# Nodo_actuador_wa4_v1.net
KiCad netlist of a schematic drawn in EAGLE
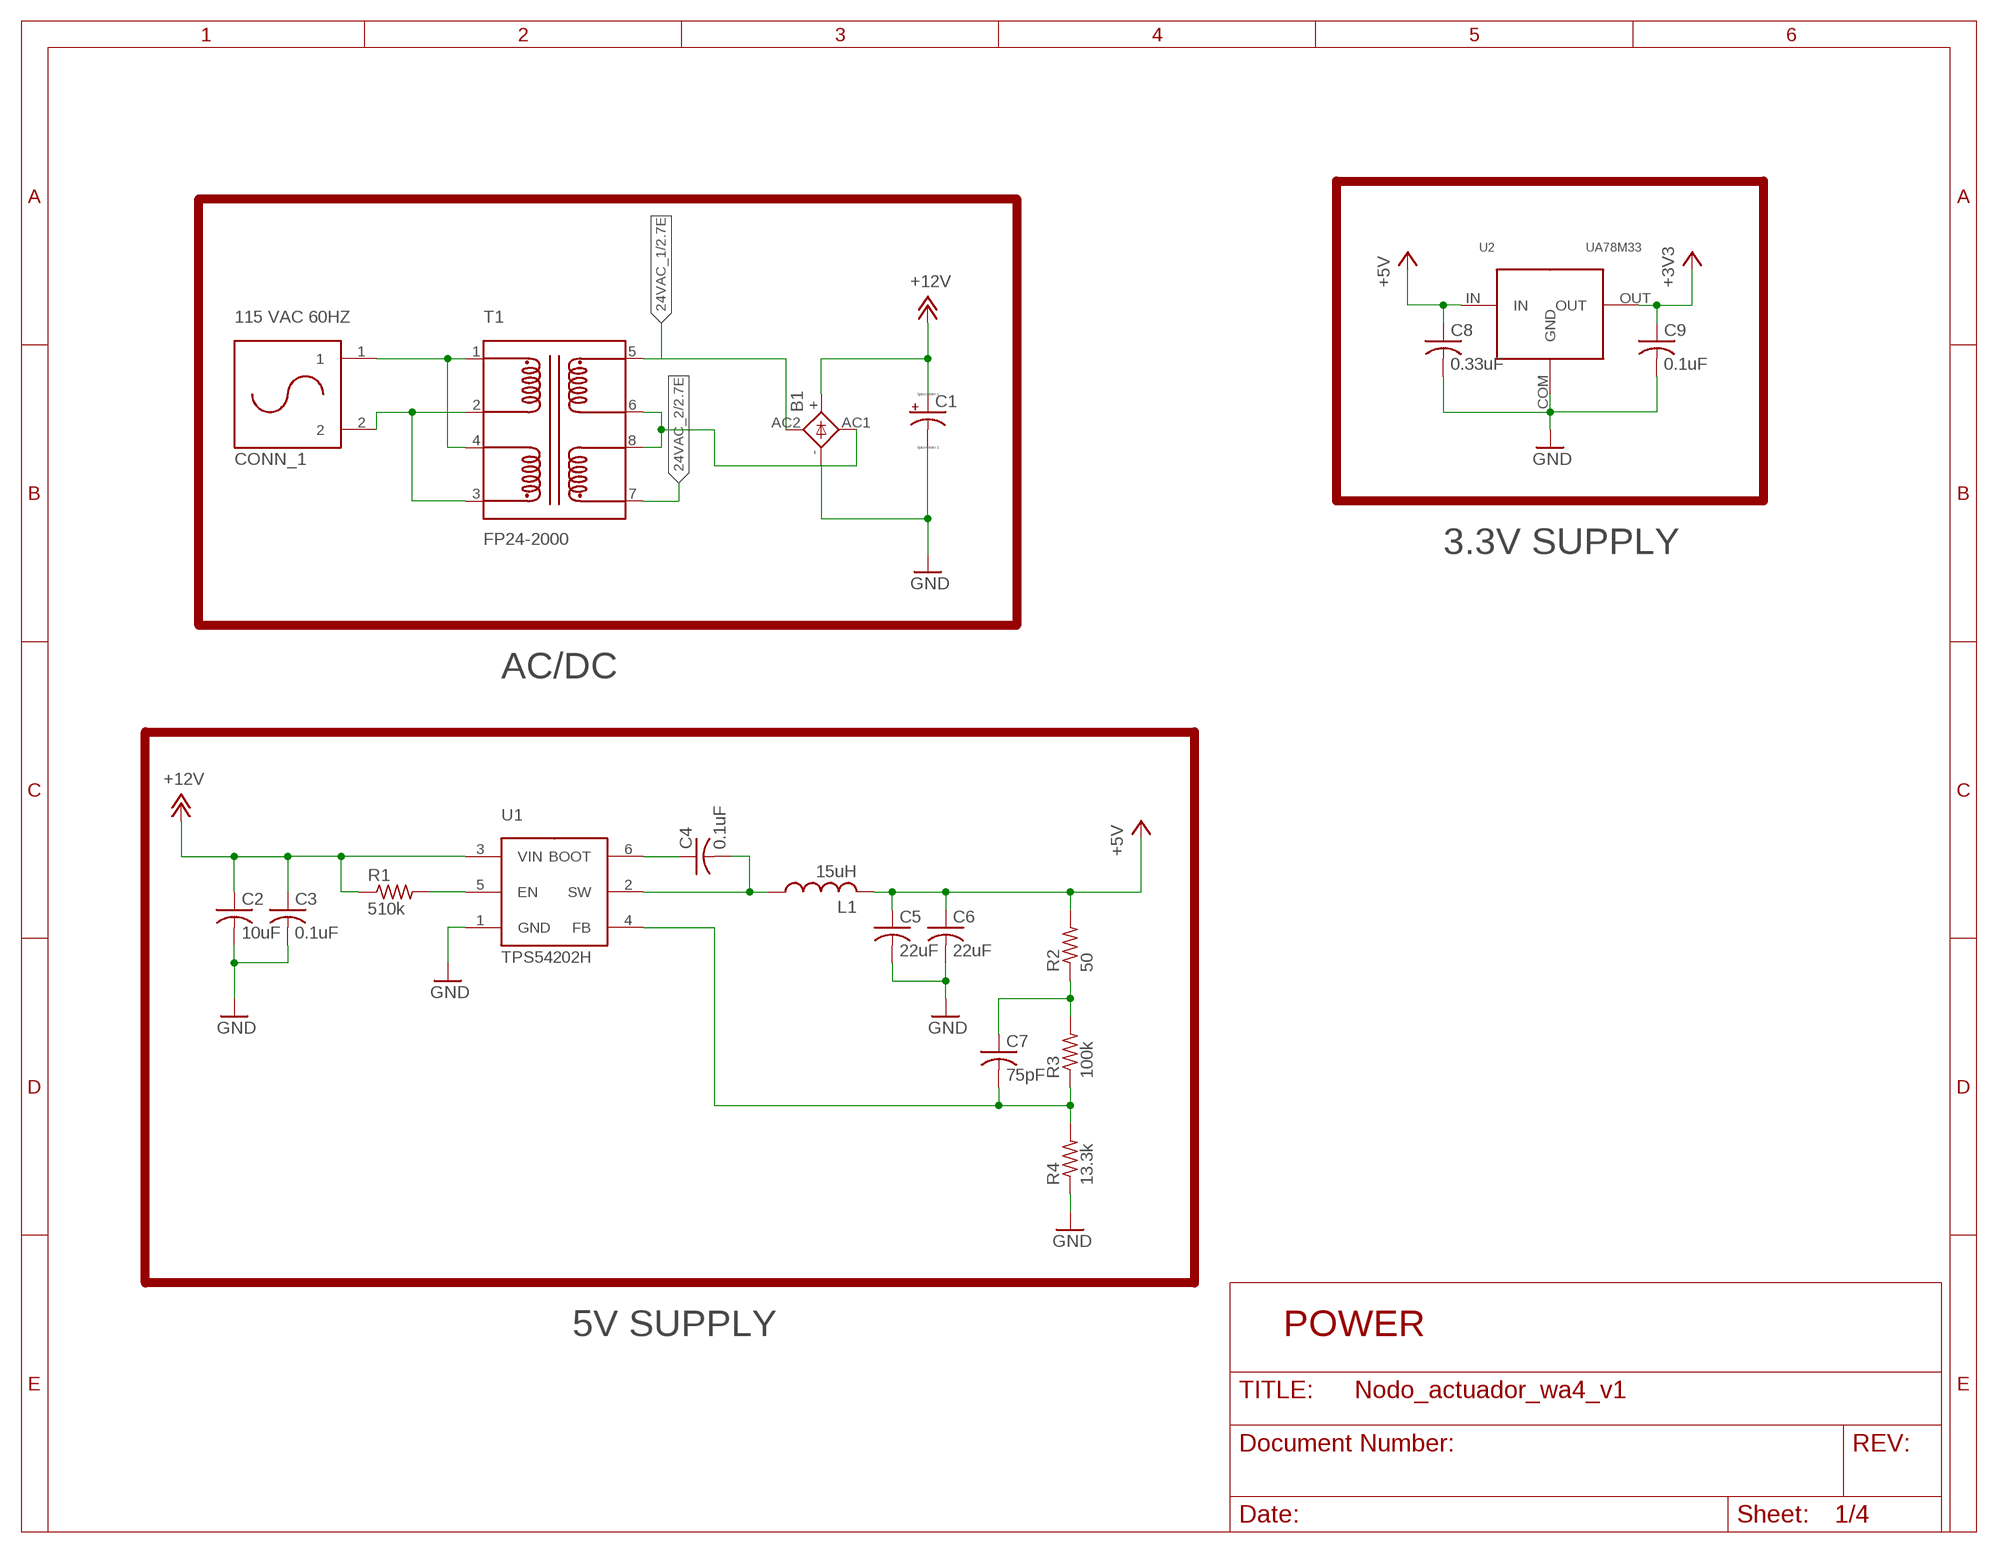
[diagram p0: schematic, sheet 1]
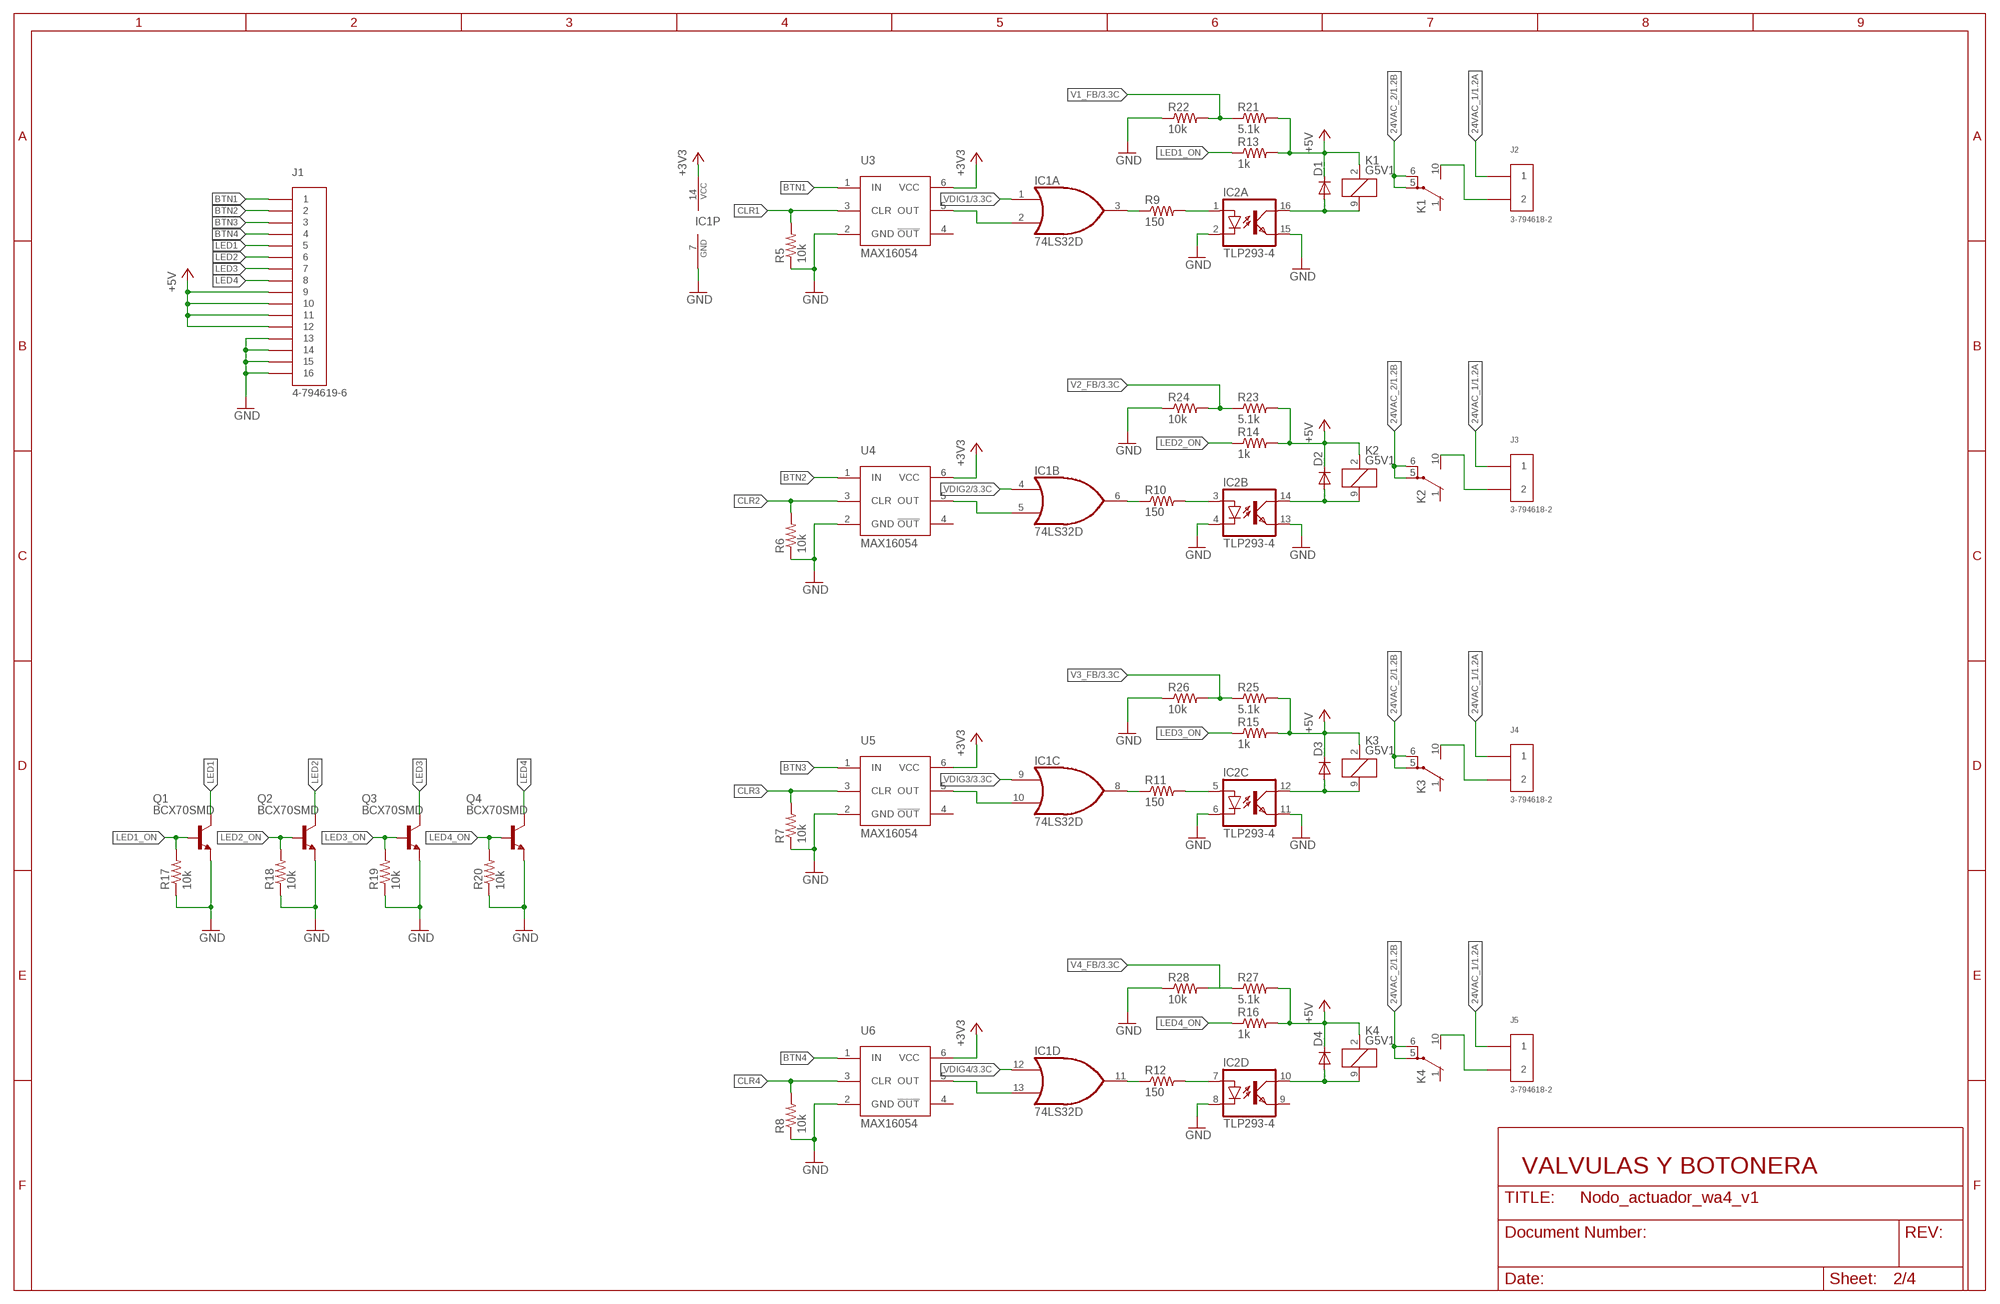
[diagram p1: schematic, sheet 2]
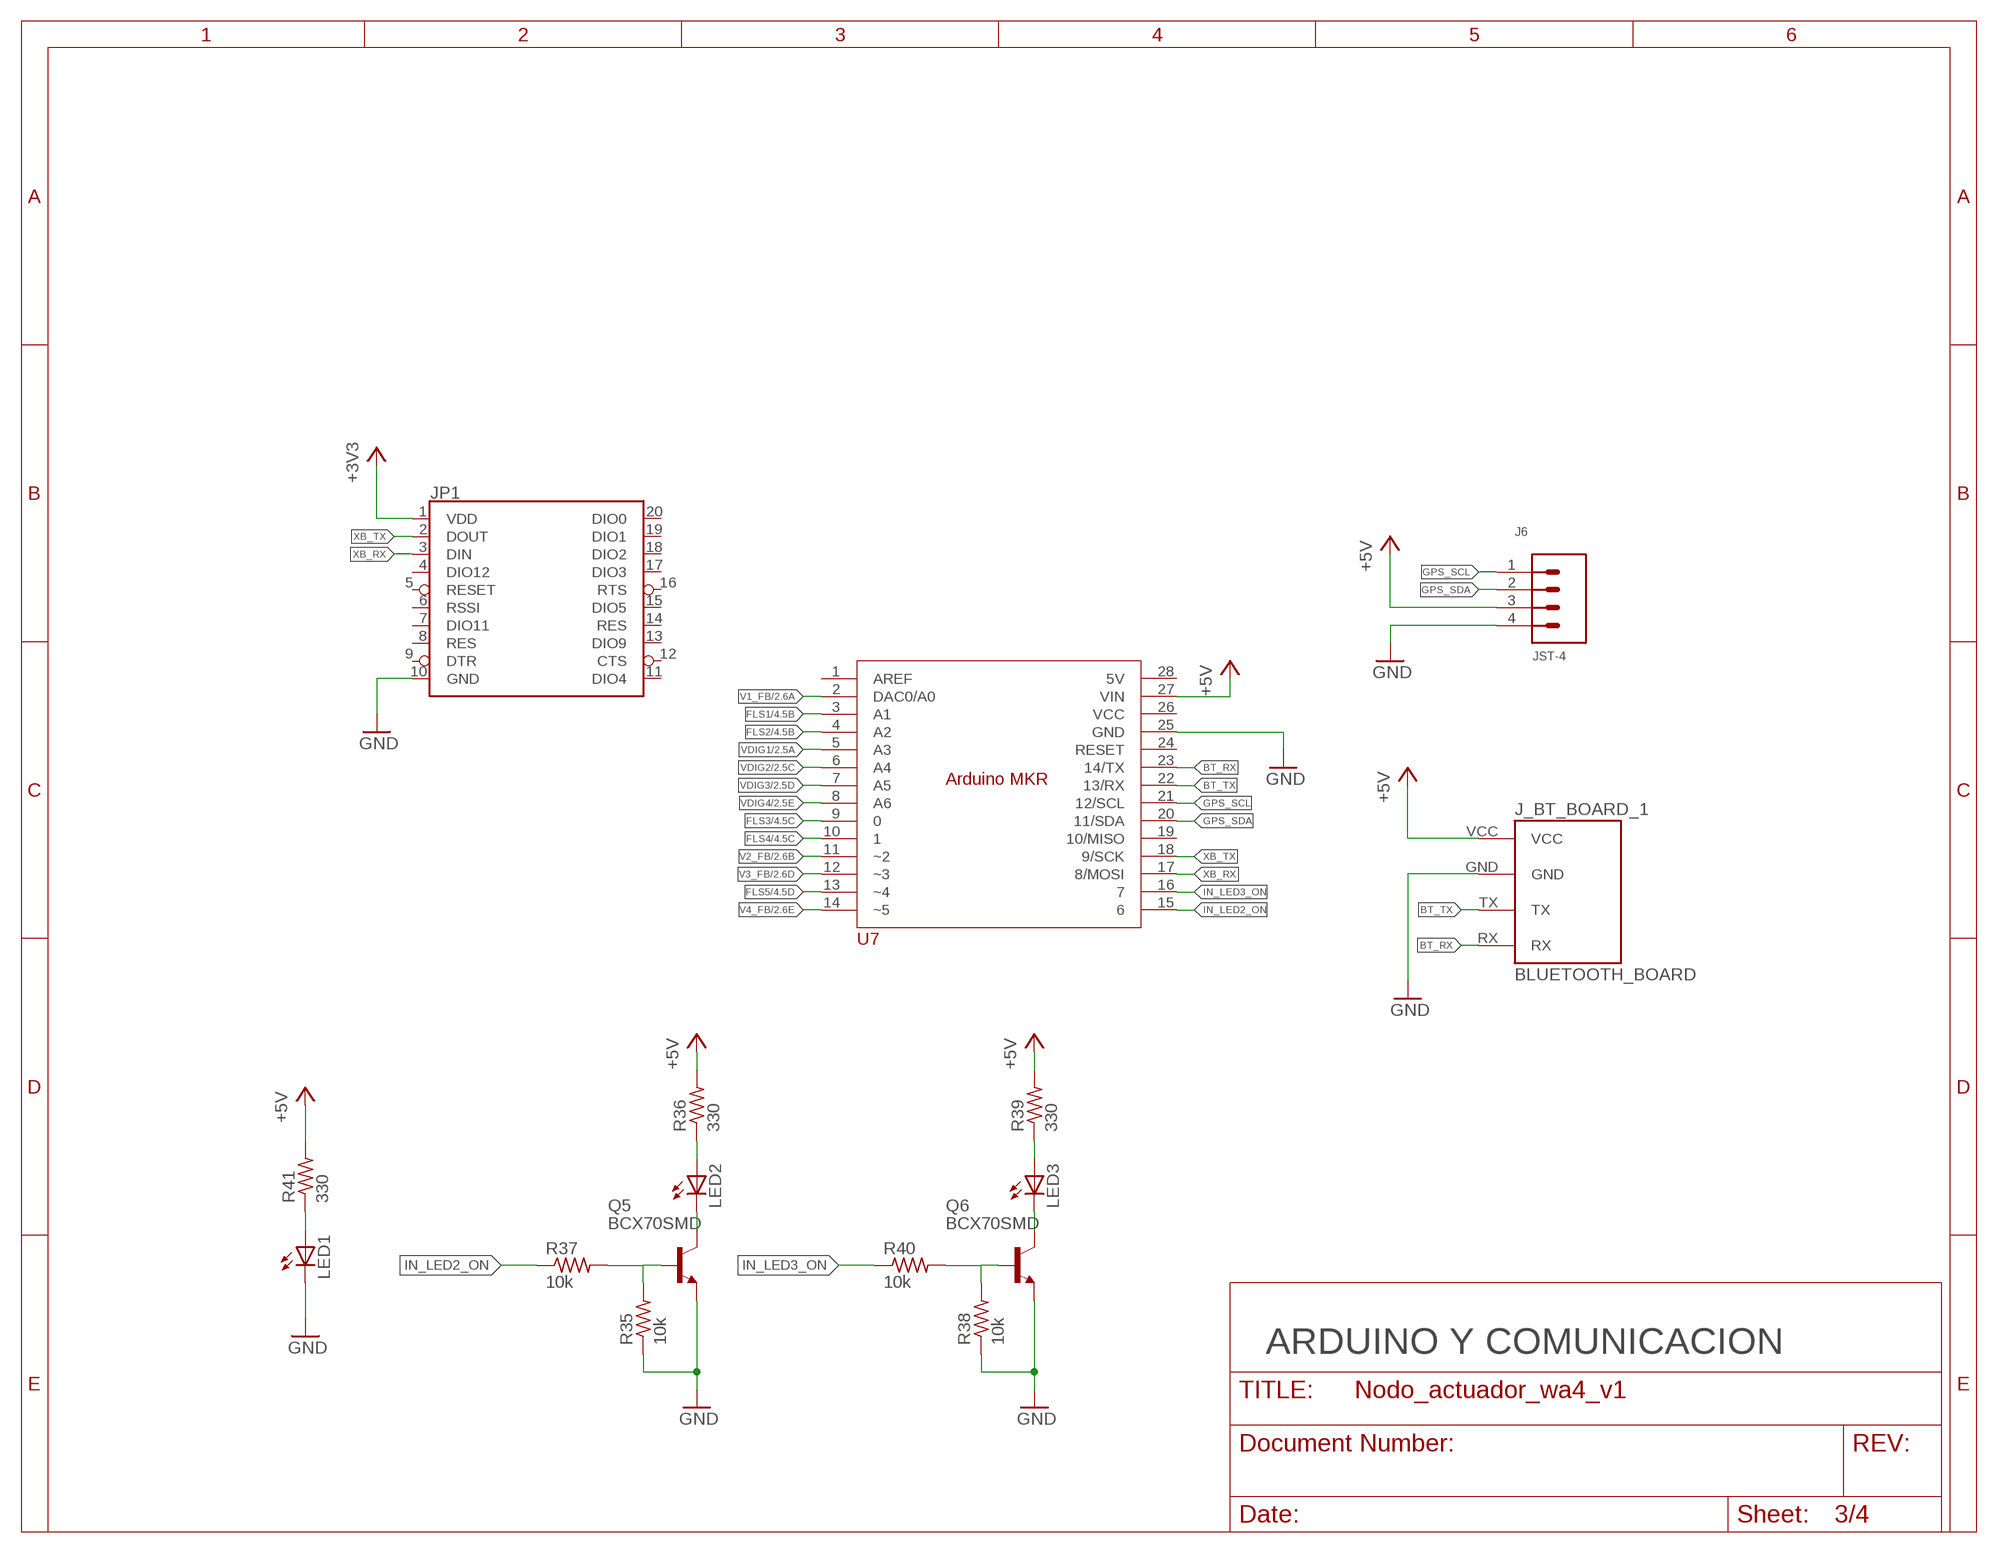
[diagram p2: schematic, sheet 3]
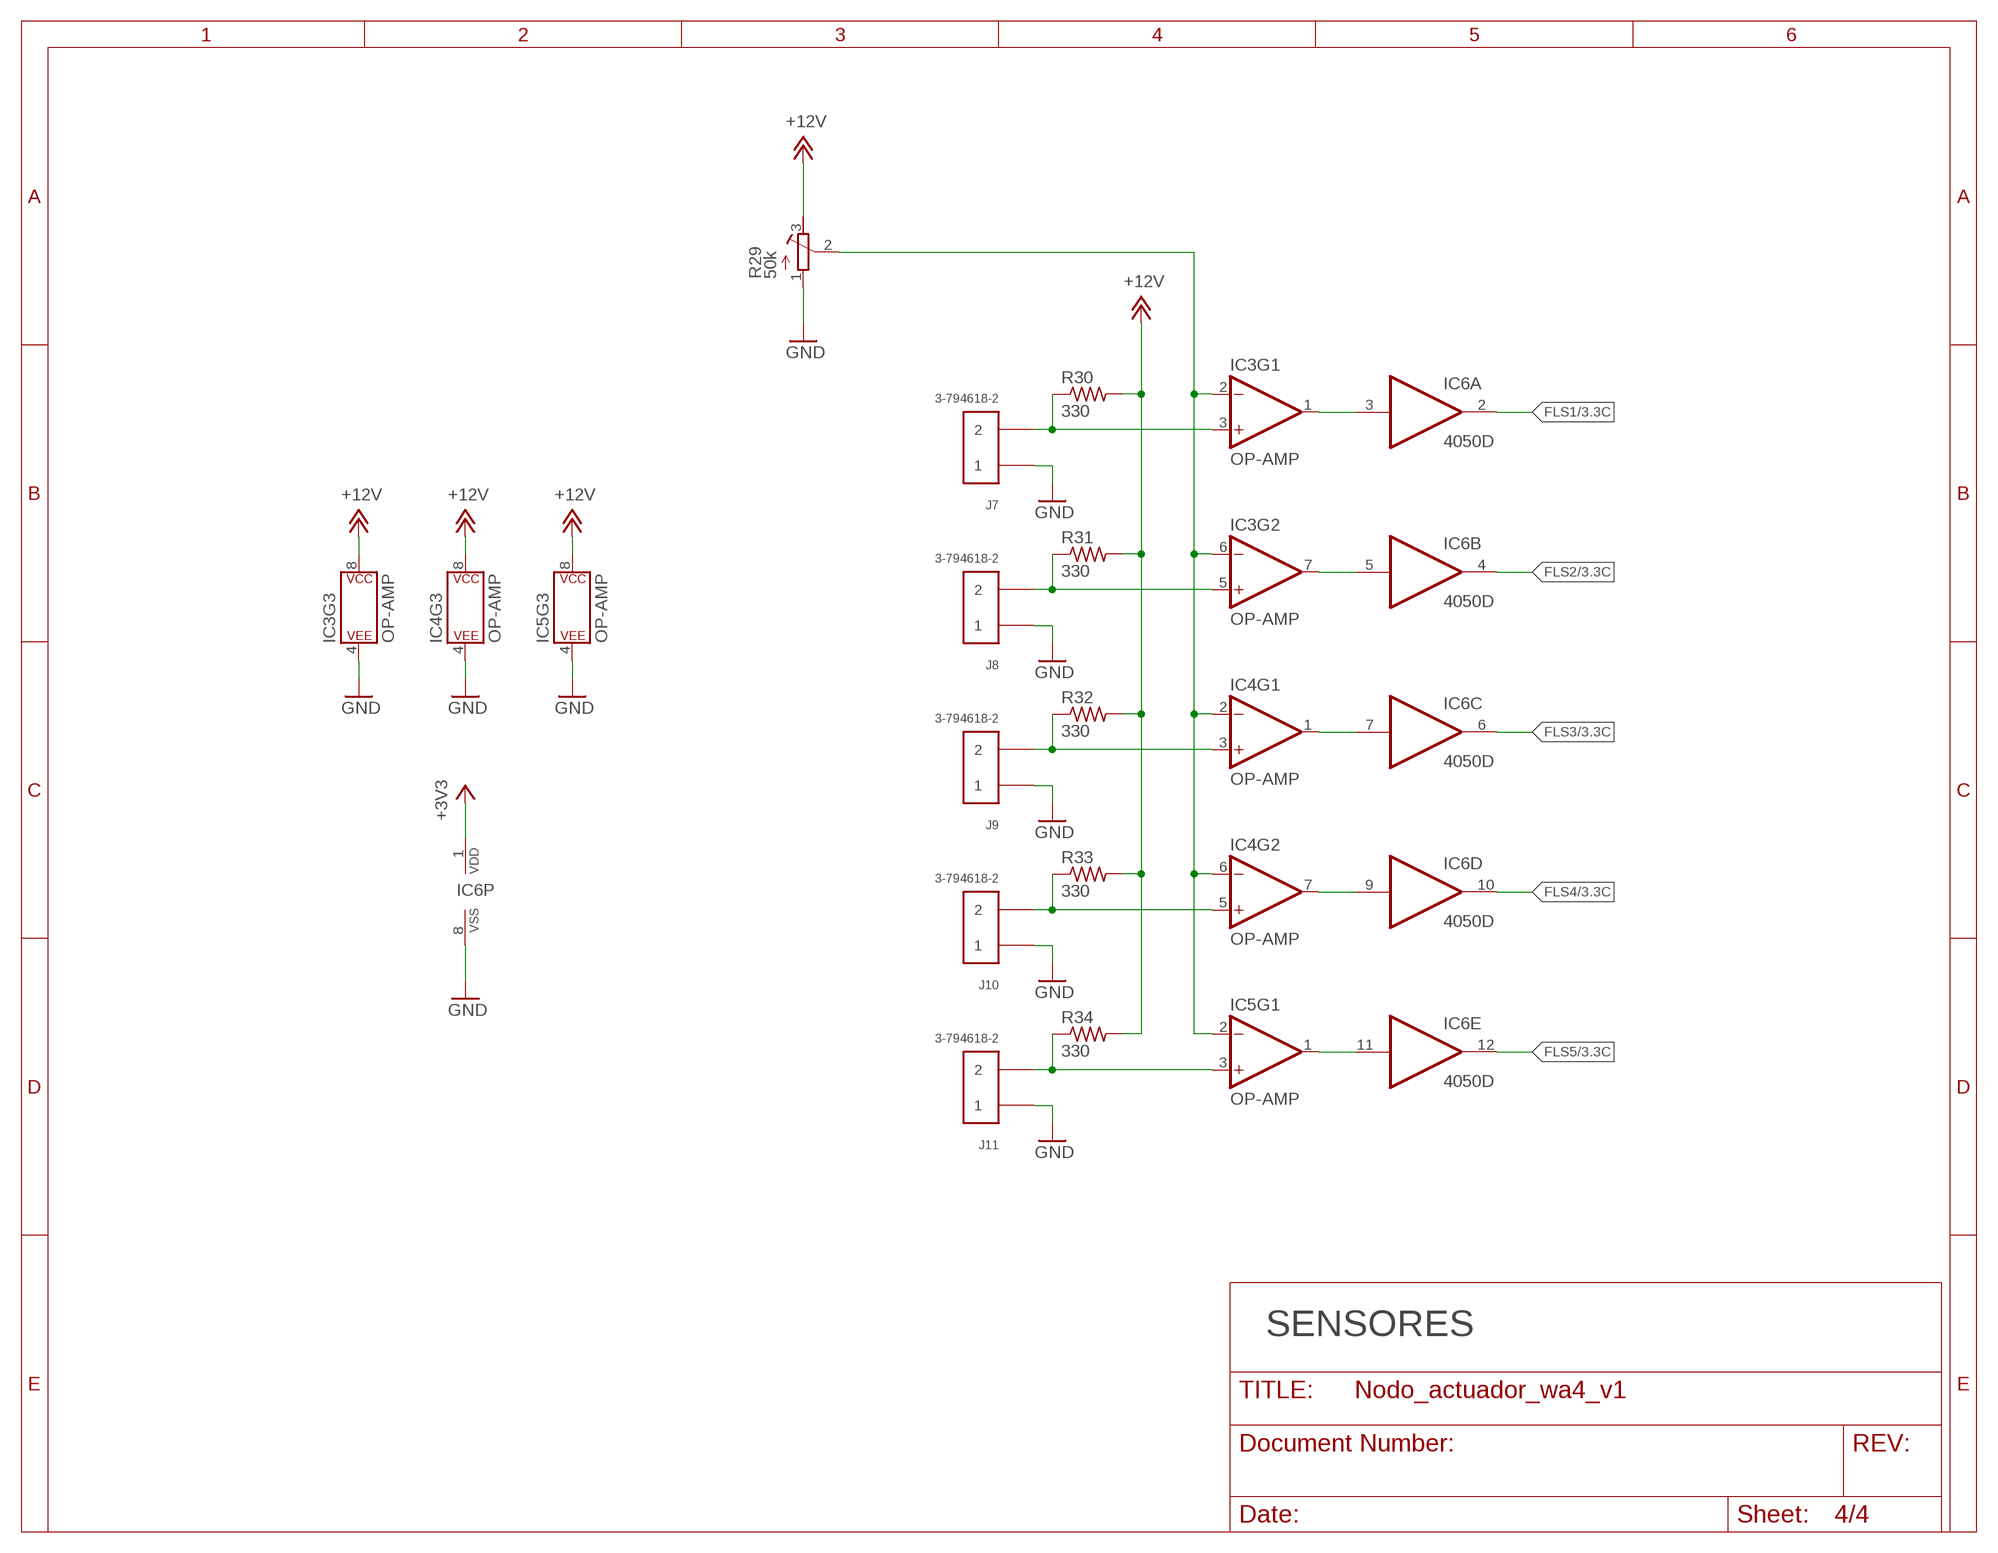
[diagram p3: schematic, sheet 4]

(export (version "E")
  (design (tool "Eeschema 10.0.6"))
  (components
    (comp (ref "D1")
      (value "MBR0520LT")
      (footprint "eagle-import:SOD123")
      (libsource (lib "eagle-import") (part "MBR0520LT"))
    )
    (comp (ref "D2")
      (value "MBR0520LT")
      (footprint "eagle-import:SOD123")
      (libsource (lib "eagle-import") (part "MBR0520LT"))
    )
    (comp (ref "D3")
      (value "MBR0520LT")
      (footprint "eagle-import:SOD123")
      (libsource (lib "eagle-import") (part "MBR0520LT"))
    )
    (comp (ref "D4")
      (value "MBR0520LT")
      (footprint "eagle-import:SOD123")
      (libsource (lib "eagle-import") (part "MBR0520LT"))
    )
    (comp (ref "IC1")
      (value "74LS32D")
      (footprint "eagle-import:SO14")
      (libsource (lib "eagle-import") (part "7432DLS"))
    )
    (comp (ref "IC2")
      (value "TLP293-4")
      (footprint "eagle-import:SO16")
      (libsource (lib "eagle-import") (part "TLP293-4"))
    )
    (comp (ref "J1")
      (value "4-794619-6")
      (footprint "eagle-import:4-794619-6")
      (libsource (lib "eagle-import") (part "4-794619-6"))
    )
    (comp (ref "J2")
      (value "3-794618-2")
      (footprint "eagle-import:3-794618-2")
      (libsource (lib "eagle-import") (part "3-794618-2"))
    )
    (comp (ref "J3")
      (value "3-794618-2")
      (footprint "eagle-import:3-794618-2")
      (libsource (lib "eagle-import") (part "3-794618-2"))
    )
    (comp (ref "J4")
      (value "3-794618-2")
      (footprint "eagle-import:3-794618-2")
      (libsource (lib "eagle-import") (part "3-794618-2"))
    )
    (comp (ref "J5")
      (value "3-794618-2")
      (footprint "eagle-import:3-794618-2")
      (libsource (lib "eagle-import") (part "3-794618-2"))
    )
    (comp (ref "K1")
      (value "G5V1")
      (footprint "eagle-import:G5V1")
      (fields (field (name "MPN") "G5V-1-DC24"))
      (libsource (lib "eagle-import") (part "G5V1"))
    )
    (comp (ref "K2")
      (value "G5V1")
      (footprint "eagle-import:G5V1")
      (fields (field (name "MPN") "G5V-1-DC24"))
      (libsource (lib "eagle-import") (part "G5V1"))
    )
    (comp (ref "K3")
      (value "G5V1")
      (footprint "eagle-import:G5V1")
      (fields (field (name "MPN") "G5V-1-DC24"))
      (libsource (lib "eagle-import") (part "G5V1"))
    )
    (comp (ref "K4")
      (value "G5V1")
      (footprint "eagle-import:G5V1")
      (fields (field (name "MPN") "G5V-1-DC24"))
      (libsource (lib "eagle-import") (part "G5V1"))
    )
    (comp (ref "Q1")
      (value "BCX70SMD")
      (footprint "eagle-import:SOT23")
      (libsource (lib "eagle-import") (part "BCX70SMD"))
    )
    (comp (ref "Q2")
      (value "BCX70SMD")
      (footprint "eagle-import:SOT23")
      (libsource (lib "eagle-import") (part "BCX70SMD"))
    )
    (comp (ref "Q3")
      (value "BCX70SMD")
      (footprint "eagle-import:SOT23")
      (libsource (lib "eagle-import") (part "BCX70SMD"))
    )
    (comp (ref "Q4")
      (value "BCX70SMD")
      (footprint "eagle-import:SOT23")
      (libsource (lib "eagle-import") (part "BCX70SMD"))
    )
    (comp (ref "R5")
      (value "10k")
      (footprint "eagle-import:R0805")
      (libsource (lib "eagle-import") (part "R-US_R0805"))
    )
    (comp (ref "R6")
      (value "10k")
      (footprint "eagle-import:R0805")
      (libsource (lib "eagle-import") (part "R-US_R0805"))
    )
    (comp (ref "R7")
      (value "10k")
      (footprint "eagle-import:R0805")
      (libsource (lib "eagle-import") (part "R-US_R0805"))
    )
    (comp (ref "R8")
      (value "10k")
      (footprint "eagle-import:R0805")
      (libsource (lib "eagle-import") (part "R-US_R0805"))
    )
    (comp (ref "R9")
      (value "150")
      (footprint "eagle-import:R0805")
      (libsource (lib "eagle-import") (part "R-US_R0805"))
    )
    (comp (ref "R10")
      (value "150")
      (footprint "eagle-import:R0805")
      (libsource (lib "eagle-import") (part "R-US_R0805"))
    )
    (comp (ref "R11")
      (value "150")
      (footprint "eagle-import:R0805")
      (libsource (lib "eagle-import") (part "R-US_R0805"))
    )
    (comp (ref "R12")
      (value "150")
      (footprint "eagle-import:R0805")
      (libsource (lib "eagle-import") (part "R-US_R0805"))
    )
    (comp (ref "R13")
      (value "1k")
      (footprint "eagle-import:R0805")
      (libsource (lib "eagle-import") (part "R-US_R0805"))
    )
    (comp (ref "R14")
      (value "1k")
      (footprint "eagle-import:R0805")
      (libsource (lib "eagle-import") (part "R-US_R0805"))
    )
    (comp (ref "R15")
      (value "1k")
      (footprint "eagle-import:R0805")
      (libsource (lib "eagle-import") (part "R-US_R0805"))
    )
    (comp (ref "R16")
      (value "1k")
      (footprint "eagle-import:R0805")
      (libsource (lib "eagle-import") (part "R-US_R0805"))
    )
    (comp (ref "R17")
      (value "10k")
      (footprint "eagle-import:R0805")
      (libsource (lib "eagle-import") (part "R-US_R0805"))
    )
    (comp (ref "R18")
      (value "10k")
      (footprint "eagle-import:R0805")
      (libsource (lib "eagle-import") (part "R-US_R0805"))
    )
    (comp (ref "R19")
      (value "10k")
      (footprint "eagle-import:R0805")
      (libsource (lib "eagle-import") (part "R-US_R0805"))
    )
    (comp (ref "R20")
      (value "10k")
      (footprint "eagle-import:R0805")
      (libsource (lib "eagle-import") (part "R-US_R0805"))
    )
    (comp (ref "R21")
      (value "5.1k")
      (footprint "eagle-import:R0805")
      (libsource (lib "eagle-import") (part "R-US_R0805"))
    )
    (comp (ref "R22")
      (value "10k")
      (footprint "eagle-import:R0805")
      (libsource (lib "eagle-import") (part "R-US_R0805"))
    )
    (comp (ref "R23")
      (value "5.1k")
      (footprint "eagle-import:R0805")
      (libsource (lib "eagle-import") (part "R-US_R0805"))
    )
    (comp (ref "R24")
      (value "10k")
      (footprint "eagle-import:R0805")
      (libsource (lib "eagle-import") (part "R-US_R0805"))
    )
    (comp (ref "R25")
      (value "5.1k")
      (footprint "eagle-import:R0805")
      (libsource (lib "eagle-import") (part "R-US_R0805"))
    )
    (comp (ref "R26")
      (value "10k")
      (footprint "eagle-import:R0805")
      (libsource (lib "eagle-import") (part "R-US_R0805"))
    )
    (comp (ref "R27")
      (value "5.1k")
      (footprint "eagle-import:R0805")
      (libsource (lib "eagle-import") (part "R-US_R0805"))
    )
    (comp (ref "R28")
      (value "10k")
      (footprint "eagle-import:R0805")
      (libsource (lib "eagle-import") (part "R-US_R0805"))
    )
    (comp (ref "U3")
      (value "MAX16054")
      (footprint "eagle-import:SOT-23-6")
      (libsource (lib "eagle-import") (part "MAX16054"))
    )
    (comp (ref "U4")
      (value "MAX16054")
      (footprint "eagle-import:SOT-23-6")
      (libsource (lib "eagle-import") (part "MAX16054"))
    )
    (comp (ref "U5")
      (value "MAX16054")
      (footprint "eagle-import:SOT-23-6")
      (libsource (lib "eagle-import") (part "MAX16054"))
    )
    (comp (ref "U6")
      (value "MAX16054")
      (footprint "eagle-import:SOT-23-6")
      (libsource (lib "eagle-import") (part "MAX16054"))
    )
    (comp (ref "J6")
      (value "JST-4")
      (footprint "eagle-import:JST-4")
      (libsource (lib "eagle-import") (part "JST-4"))
    )
    (comp (ref "JP1")
      (value "XBEESILK")
      (footprint "eagle-import:XBEE-SILK")
      (libsource (lib "eagle-import") (part "XBEESILK"))
    )
    (comp (ref "J_BT_BOARD_1")
      (value "BLUETOOTH_BOARD")
      (footprint "eagle-import:BT_BOARD_FOOTPRINT")
      (libsource (lib "eagle-import") (part "BLUETOOTH_BOARD"))
    )
    (comp (ref "LED1")
      (value "LEDCHIP-LED0805")
      (footprint "eagle-import:CHIP-LED0805")
      (libsource (lib "eagle-import") (part "LEDCHIP-LED0805"))
    )
    (comp (ref "LED2")
      (value "LEDCHIP-LED0805")
      (footprint "eagle-import:CHIP-LED0805")
      (libsource (lib "eagle-import") (part "LEDCHIP-LED0805"))
    )
    (comp (ref "LED3")
      (value "LEDCHIP-LED0805")
      (footprint "eagle-import:CHIP-LED0805")
      (libsource (lib "eagle-import") (part "LEDCHIP-LED0805"))
    )
    (comp (ref "Q5")
      (value "BCX70SMD")
      (footprint "eagle-import:SOT23")
      (libsource (lib "eagle-import") (part "BCX70SMD"))
    )
    (comp (ref "Q6")
      (value "BCX70SMD")
      (footprint "eagle-import:SOT23")
      (libsource (lib "eagle-import") (part "BCX70SMD"))
    )
    (comp (ref "R35")
      (value "10k")
      (footprint "eagle-import:R0805")
      (libsource (lib "eagle-import") (part "R-US_R0805"))
    )
    (comp (ref "R36")
      (value "330")
      (footprint "eagle-import:R0805")
      (libsource (lib "eagle-import") (part "R-US_R0805"))
    )
    (comp (ref "R37")
      (value "10k")
      (footprint "eagle-import:R0805")
      (libsource (lib "eagle-import") (part "R-US_R0805"))
    )
    (comp (ref "R38")
      (value "10k")
      (footprint "eagle-import:R0805")
      (libsource (lib "eagle-import") (part "R-US_R0805"))
    )
    (comp (ref "R39")
      (value "330")
      (footprint "eagle-import:R0805")
      (libsource (lib "eagle-import") (part "R-US_R0805"))
    )
    (comp (ref "R40")
      (value "10k")
      (footprint "eagle-import:R0805")
      (libsource (lib "eagle-import") (part "R-US_R0805"))
    )
    (comp (ref "R41")
      (value "330")
      (footprint "eagle-import:R0805")
      (libsource (lib "eagle-import") (part "R-US_R0805"))
    )
    (comp (ref "U7")
      (value "ARDUINO_MKR")
      (footprint "eagle-import:ARDUINO_MKR")
      (libsource (lib "eagle-import") (part "ARDUINO_MKR"))
    )
    (comp (ref "B1")
      (value "GBU4")
      (footprint "eagle-import:GBU4S")
      (libsource (lib "eagle-import") (part "GBU4"))
    )
    (comp (ref "C1")
      (value "CPOL-USE5-13")
      (footprint "eagle-import:E5-13")
      (libsource (lib "eagle-import") (part "CPOL-USE5-13"))
    )
    (comp (ref "C2")
      (value "10uF")
      (footprint "eagle-import:C0805")
      (libsource (lib "eagle-import") (part "C-USC0805"))
    )
    (comp (ref "C3")
      (value "0.1uF")
      (footprint "eagle-import:C0805")
      (libsource (lib "eagle-import") (part "C-USC0805"))
    )
    (comp (ref "C4")
      (value "0.1uF")
      (footprint "eagle-import:C0805")
      (libsource (lib "eagle-import") (part "C-USC0805"))
    )
    (comp (ref "C5")
      (value "22uF")
      (footprint "eagle-import:C0805")
      (libsource (lib "eagle-import") (part "C-USC0805"))
    )
    (comp (ref "C6")
      (value "22uF")
      (footprint "eagle-import:C0805")
      (libsource (lib "eagle-import") (part "C-USC0805"))
    )
    (comp (ref "C7")
      (value "75pF")
      (footprint "eagle-import:C0805")
      (libsource (lib "eagle-import") (part "C-USC0805"))
    )
    (comp (ref "C8")
      (value "0.33uF")
      (footprint "eagle-import:C0805")
      (libsource (lib "eagle-import") (part "C-USC0805"))
    )
    (comp (ref "C9")
      (value "0.1uF")
      (footprint "eagle-import:C0805")
      (libsource (lib "eagle-import") (part "C-USC0805"))
    )
    (comp (ref "CONN_1")
      (value "115 VAC 60HZ")
      (footprint "eagle-import:2570-2210")
      (libsource (lib "eagle-import") (part "2570-2210"))
    )
    (comp (ref "L1")
      (value "15uH")
      (footprint "eagle-import:VLS5045")
      (libsource (lib "eagle-import") (part "VLS5045EX"))
    )
    (comp (ref "R1")
      (value "510k")
      (footprint "eagle-import:R0805")
      (libsource (lib "eagle-import") (part "R-US_R0805"))
    )
    (comp (ref "R2")
      (value "50")
      (footprint "eagle-import:R0805")
      (libsource (lib "eagle-import") (part "R-US_R0805"))
    )
    (comp (ref "R3")
      (value "100k")
      (footprint "eagle-import:R0805")
      (libsource (lib "eagle-import") (part "R-US_R0805"))
    )
    (comp (ref "R4")
      (value "13.3k")
      (footprint "eagle-import:R0805")
      (libsource (lib "eagle-import") (part "R-US_R0805"))
    )
    (comp (ref "T1")
      (value "FP24-2000")
      (footprint "eagle-import:FP24-2000")
      (libsource (lib "eagle-import") (part "FP24-2000"))
    )
    (comp (ref "U1")
      (value "TPS54202H")
      (footprint "eagle-import:SOT-23-6")
      (libsource (lib "eagle-import") (part "TPS54202H"))
    )
    (comp (ref "U2")
      (value "UA78M33")
      (footprint "eagle-import:UA78XX")
      (libsource (lib "eagle-import") (part "UA78M33"))
    )
    (comp (ref "IC3")
      (value "OP-AMP")
      (footprint "eagle-import:SO08")
      (libsource (lib "eagle-import") (part "OPAMP-DUALU"))
    )
    (comp (ref "IC4")
      (value "OP-AMP")
      (footprint "eagle-import:SO08")
      (libsource (lib "eagle-import") (part "OPAMP-DUALU"))
    )
    (comp (ref "IC5")
      (value "OP-AMP")
      (footprint "eagle-import:SO08")
      (libsource (lib "eagle-import") (part "OPAMP-DUALU"))
    )
    (comp (ref "IC6")
      (value "4050D")
      (footprint "eagle-import:SO16")
      (libsource (lib "eagle-import") (part "4050D"))
    )
    (comp (ref "J7")
      (value "3-794618-2")
      (footprint "eagle-import:3-794618-2")
      (libsource (lib "eagle-import") (part "3-794618-2"))
    )
    (comp (ref "J8")
      (value "3-794618-2")
      (footprint "eagle-import:3-794618-2")
      (libsource (lib "eagle-import") (part "3-794618-2"))
    )
    (comp (ref "J9")
      (value "3-794618-2")
      (footprint "eagle-import:3-794618-2")
      (libsource (lib "eagle-import") (part "3-794618-2"))
    )
    (comp (ref "J10")
      (value "3-794618-2")
      (footprint "eagle-import:3-794618-2")
      (libsource (lib "eagle-import") (part "3-794618-2"))
    )
    (comp (ref "J11")
      (value "3-794618-2")
      (footprint "eagle-import:3-794618-2")
      (libsource (lib "eagle-import") (part "3-794618-2"))
    )
    (comp (ref "R29")
      (value "50k")
      (footprint "eagle-import:RTRIM3224W")
      (libsource (lib "eagle-import") (part "R-TRIMM3224W"))
    )
    (comp (ref "R30")
      (value "330")
      (footprint "eagle-import:R0805")
      (libsource (lib "eagle-import") (part "R-US_R0805"))
    )
    (comp (ref "R31")
      (value "330")
      (footprint "eagle-import:R0805")
      (libsource (lib "eagle-import") (part "R-US_R0805"))
    )
    (comp (ref "R32")
      (value "330")
      (footprint "eagle-import:R0805")
      (libsource (lib "eagle-import") (part "R-US_R0805"))
    )
    (comp (ref "R33")
      (value "330")
      (footprint "eagle-import:R0805")
      (libsource (lib "eagle-import") (part "R-US_R0805"))
    )
    (comp (ref "R34")
      (value "330")
      (footprint "eagle-import:R0805")
      (libsource (lib "eagle-import") (part "R-US_R0805"))
    )
  )
  (nets
    (net (code "1") (name "+3V3") (class "Default")
      (node (ref "C9") (pin "1") (pinfunction "1_1") (pintype "passive"))
      (node (ref "IC1") (pin "14") (pinfunction "VCC_14") (pintype "power_in"))
      (node (ref "IC6") (pin "1") (pinfunction "VDD_1") (pintype "power_in"))
      (node (ref "JP1") (pin "1") (pinfunction "VDD_1") (pintype "power_in"))
      (node (ref "U2") (pin "OUT") (pinfunction "OUT_OUT") (pintype "bidirectional"))
      (node (ref "U3") (pin "6") (pinfunction "VCC_6") (pintype "bidirectional"))
      (node (ref "U4") (pin "6") (pinfunction "VCC_6") (pintype "bidirectional"))
      (node (ref "U5") (pin "6") (pinfunction "VCC_6") (pintype "bidirectional"))
      (node (ref "U6") (pin "6") (pinfunction "VCC_6") (pintype "bidirectional"))
    )
    (net (code "2") (name "+5V") (class "Default")
      (node (ref "C5") (pin "1") (pinfunction "1_1") (pintype "passive"))
      (node (ref "C6") (pin "1") (pinfunction "1_1") (pintype "passive"))
      (node (ref "C8") (pin "1") (pinfunction "1_1") (pintype "passive"))
      (node (ref "D1") (pin "C") (pinfunction "C_C") (pintype "passive"))
      (node (ref "D2") (pin "C") (pinfunction "C_C") (pintype "passive"))
      (node (ref "D3") (pin "C") (pinfunction "C_C") (pintype "passive"))
      (node (ref "D4") (pin "C") (pinfunction "C_C") (pintype "passive"))
      (node (ref "J1") (pin "5") (pinfunction "12_5") (pintype "bidirectional"))
      (node (ref "J1") (pin "6") (pinfunction "11_6") (pintype "bidirectional"))
      (node (ref "J1") (pin "7") (pinfunction "10_7") (pintype "bidirectional"))
      (node (ref "J1") (pin "8") (pinfunction "9_8") (pintype "bidirectional"))
      (node (ref "J6") (pin "3") (pinfunction "3_3") (pintype "bidirectional"))
      (node (ref "J_BT_BOARD_1") (pin "VCC") (pinfunction "VCC_VCC") (pintype "bidirectional"))
      (node (ref "K1") (pin "2") (pinfunction "1_2") (pintype "passive"))
      (node (ref "K2") (pin "2") (pinfunction "1_2") (pintype "passive"))
      (node (ref "K3") (pin "2") (pinfunction "1_2") (pintype "passive"))
      (node (ref "K4") (pin "2") (pinfunction "1_2") (pintype "passive"))
      (node (ref "L1") (pin "2") (pinfunction "2_2") (pintype "passive"))
      (node (ref "R13") (pin "2") (pinfunction "2_2") (pintype "passive"))
      (node (ref "R14") (pin "2") (pinfunction "2_2") (pintype "passive"))
      (node (ref "R15") (pin "2") (pinfunction "2_2") (pintype "passive"))
      (node (ref "R16") (pin "2") (pinfunction "2_2") (pintype "passive"))
      (node (ref "R2") (pin "2") (pinfunction "2_2") (pintype "passive"))
      (node (ref "R21") (pin "2") (pinfunction "2_2") (pintype "passive"))
      (node (ref "R23") (pin "2") (pinfunction "2_2") (pintype "passive"))
      (node (ref "R25") (pin "2") (pinfunction "2_2") (pintype "passive"))
      (node (ref "R27") (pin "2") (pinfunction "2_2") (pintype "passive"))
      (node (ref "R36") (pin "2") (pinfunction "2_2") (pintype "passive"))
      (node (ref "R39") (pin "2") (pinfunction "2_2") (pintype "passive"))
      (node (ref "R41") (pin "2") (pinfunction "2_2") (pintype "passive"))
      (node (ref "U2") (pin "IN") (pinfunction "IN_IN") (pintype "bidirectional"))
      (node (ref "U7") (pin "27") (pinfunction "VIN_27") (pintype "bidirectional"))
    )
    (net (code "3") (name "+12V") (class "Default")
      (node (ref "B1") (pin "+") (pinfunction "+_+") (pintype "passive"))
      (node (ref "C1") (pin "+") (pinfunction "+_+") (pintype "passive"))
      (node (ref "C2") (pin "1") (pinfunction "1_1") (pintype "passive"))
      (node (ref "C3") (pin "1") (pinfunction "1_1") (pintype "passive"))
      (node (ref "IC3") (pin "8") (pinfunction "P$V+_8") (pintype "bidirectional"))
      (node (ref "IC4") (pin "8") (pinfunction "P$V+_8") (pintype "bidirectional"))
      (node (ref "IC5") (pin "8") (pinfunction "P$V+_8") (pintype "bidirectional"))
      (node (ref "R1") (pin "1") (pinfunction "1_1") (pintype "passive"))
      (node (ref "R29") (pin "3") (pinfunction "E_3") (pintype "passive"))
      (node (ref "R30") (pin "2") (pinfunction "2_2") (pintype "passive"))
      (node (ref "R31") (pin "2") (pinfunction "2_2") (pintype "passive"))
      (node (ref "R32") (pin "2") (pinfunction "2_2") (pintype "passive"))
      (node (ref "R33") (pin "2") (pinfunction "2_2") (pintype "passive"))
      (node (ref "R34") (pin "2") (pinfunction "2_2") (pintype "passive"))
      (node (ref "U1") (pin "3") (pinfunction "VIN_3") (pintype "bidirectional"))
    )
    (net (code "4") (name "24VAC_1") (class "Default")
      (node (ref "B1") (pin "AC2") (pinfunction "AC1_AC2") (pintype "passive"))
      (node (ref "J2") (pin "1") (pinfunction "1_1") (pintype "bidirectional"))
      (node (ref "J3") (pin "1") (pinfunction "1_1") (pintype "bidirectional"))
      (node (ref "J4") (pin "1") (pinfunction "1_1") (pintype "bidirectional"))
      (node (ref "J5") (pin "1") (pinfunction "1_1") (pintype "bidirectional"))
      (node (ref "T1") (pin "5") (pinfunction "5_5") (pintype "passive"))
    )
    (net (code "5") (name "24VAC_2") (class "Default")
      (node (ref "K1") (pin "5") (pinfunction "P_5") (pintype "passive"))
      (node (ref "K1") (pin "6") (pinfunction "P_6") (pintype "passive"))
      (node (ref "K2") (pin "5") (pinfunction "P_5") (pintype "passive"))
      (node (ref "K2") (pin "6") (pinfunction "P_6") (pintype "passive"))
      (node (ref "K3") (pin "5") (pinfunction "P_5") (pintype "passive"))
      (node (ref "K3") (pin "6") (pinfunction "P_6") (pintype "passive"))
      (node (ref "K4") (pin "5") (pinfunction "P_5") (pintype "passive"))
      (node (ref "K4") (pin "6") (pinfunction "P_6") (pintype "passive"))
      (node (ref "T1") (pin "7") (pinfunction "7_7") (pintype "passive"))
    )
    (net (code "6") (name "BTN1") (class "Default")
      (node (ref "J1") (pin "16") (pinfunction "1_16") (pintype "bidirectional"))
      (node (ref "U3") (pin "1") (pinfunction "IN_1") (pintype "bidirectional"))
    )
    (net (code "7") (name "BTN2") (class "Default")
      (node (ref "J1") (pin "15") (pinfunction "2_15") (pintype "bidirectional"))
      (node (ref "U4") (pin "1") (pinfunction "IN_1") (pintype "bidirectional"))
    )
    (net (code "8") (name "BTN3") (class "Default")
      (node (ref "J1") (pin "14") (pinfunction "3_14") (pintype "bidirectional"))
      (node (ref "U5") (pin "1") (pinfunction "IN_1") (pintype "bidirectional"))
    )
    (net (code "9") (name "BTN4") (class "Default")
      (node (ref "J1") (pin "13") (pinfunction "4_13") (pintype "bidirectional"))
      (node (ref "U6") (pin "1") (pinfunction "IN_1") (pintype "bidirectional"))
    )
    (net (code "10") (name "BT_RX") (class "Default")
      (node (ref "J_BT_BOARD_1") (pin "RX") (pinfunction "RX_RX") (pintype "bidirectional"))
      (node (ref "U7") (pin "23") (pinfunction "14/TX_23") (pintype "bidirectional"))
    )
    (net (code "11") (name "BT_TX") (class "Default")
      (node (ref "J_BT_BOARD_1") (pin "TX") (pinfunction "TX_TX") (pintype "bidirectional"))
      (node (ref "U7") (pin "22") (pinfunction "13/RX_22") (pintype "bidirectional"))
    )
    (net (code "12") (name "CLR1") (class "Default")
      (node (ref "R5") (pin "2") (pinfunction "2_2") (pintype "passive"))
      (node (ref "U3") (pin "3") (pinfunction "CLR_3") (pintype "bidirectional"))
    )
    (net (code "13") (name "CLR2") (class "Default")
      (node (ref "R6") (pin "2") (pinfunction "2_2") (pintype "passive"))
      (node (ref "U4") (pin "3") (pinfunction "CLR_3") (pintype "bidirectional"))
    )
    (net (code "14") (name "CLR3") (class "Default")
      (node (ref "R7") (pin "2") (pinfunction "2_2") (pintype "passive"))
      (node (ref "U5") (pin "3") (pinfunction "CLR_3") (pintype "bidirectional"))
    )
    (net (code "15") (name "CLR4") (class "Default")
      (node (ref "R8") (pin "2") (pinfunction "2_2") (pintype "passive"))
      (node (ref "U6") (pin "3") (pinfunction "CLR_3") (pintype "bidirectional"))
    )
    (net (code "16") (name "FLS1") (class "Default")
      (node (ref "IC6") (pin "2") (pinfunction "O_2") (pintype "output"))
      (node (ref "U7") (pin "3") (pinfunction "A1_3") (pintype "bidirectional"))
    )
    (net (code "17") (name "FLS2") (class "Default")
      (node (ref "IC6") (pin "4") (pinfunction "O_4") (pintype "output"))
      (node (ref "U7") (pin "4") (pinfunction "A2_4") (pintype "bidirectional"))
    )
    (net (code "18") (name "FLS3") (class "Default")
      (node (ref "IC6") (pin "6") (pinfunction "O_6") (pintype "output"))
      (node (ref "U7") (pin "9") (pinfunction "0_9") (pintype "bidirectional"))
    )
    (net (code "19") (name "FLS4") (class "Default")
      (node (ref "IC6") (pin "10") (pinfunction "O_10") (pintype "output"))
      (node (ref "U7") (pin "10") (pinfunction "1_10") (pintype "bidirectional"))
    )
    (net (code "20") (name "FLS5") (class "Default")
      (node (ref "IC6") (pin "12") (pinfunction "O_12") (pintype "output"))
      (node (ref "U7") (pin "13") (pinfunction "~{4}_13") (pintype "bidirectional"))
    )
    (net (code "21") (name "GND") (class "Default")
      (node (ref "B1") (pin "-") (pinfunction "-_-") (pintype "passive"))
      (node (ref "C1") (pin "-") (pinfunction "-_-") (pintype "passive"))
      (node (ref "C2") (pin "2") (pinfunction "2_2") (pintype "passive"))
      (node (ref "C3") (pin "2") (pinfunction "2_2") (pintype "passive"))
      (node (ref "C5") (pin "2") (pinfunction "2_2") (pintype "passive"))
      (node (ref "C6") (pin "2") (pinfunction "2_2") (pintype "passive"))
      (node (ref "C8") (pin "2") (pinfunction "2_2") (pintype "passive"))
      (node (ref "C9") (pin "2") (pinfunction "2_2") (pintype "passive"))
      (node (ref "IC1") (pin "7") (pinfunction "GND_7") (pintype "power_in"))
      (node (ref "IC2") (pin "11") (pinfunction "EMIT_11") (pintype "passive"))
      (node (ref "IC2") (pin "13") (pinfunction "EMIT_13") (pintype "passive"))
      (node (ref "IC2") (pin "15") (pinfunction "EMIT_15") (pintype "passive"))
      (node (ref "IC2") (pin "2") (pinfunction "C_2") (pintype "passive"))
      (node (ref "IC2") (pin "4") (pinfunction "C_4") (pintype "passive"))
      (node (ref "IC2") (pin "6") (pinfunction "C_6") (pintype "passive"))
      (node (ref "IC2") (pin "8") (pinfunction "C_8") (pintype "passive"))
      (node (ref "IC3") (pin "4") (pinfunction "P$V-_4") (pintype "bidirectional"))
      (node (ref "IC4") (pin "4") (pinfunction "P$V-_4") (pintype "bidirectional"))
      (node (ref "IC5") (pin "4") (pinfunction "P$V-_4") (pintype "bidirectional"))
      (node (ref "IC6") (pin "8") (pinfunction "VSS_8") (pintype "power_in"))
      (node (ref "J1") (pin "1") (pinfunction "16_1") (pintype "bidirectional"))
      (node (ref "J1") (pin "2") (pinfunction "15_2") (pintype "bidirectional"))
      (node (ref "J1") (pin "3") (pinfunction "14_3") (pintype "bidirectional"))
      (node (ref "J1") (pin "4") (pinfunction "13_4") (pintype "bidirectional"))
      (node (ref "J10") (pin "1") (pinfunction "1_1") (pintype "bidirectional"))
      (node (ref "J11") (pin "1") (pinfunction "1_1") (pintype "bidirectional"))
      (node (ref "J6") (pin "4") (pinfunction "4_4") (pintype "bidirectional"))
      (node (ref "J7") (pin "1") (pinfunction "1_1") (pintype "bidirectional"))
      (node (ref "J8") (pin "1") (pinfunction "1_1") (pintype "bidirectional"))
      (node (ref "J9") (pin "1") (pinfunction "1_1") (pintype "bidirectional"))
      (node (ref "JP1") (pin "10") (pinfunction "GND_10") (pintype "power_in"))
      (node (ref "J_BT_BOARD_1") (pin "GND") (pinfunction "GND_GND") (pintype "bidirectional"))
      (node (ref "LED1") (pin "C") (pinfunction "C_C") (pintype "passive"))
      (node (ref "Q1") (pin "2") (pinfunction "E_2") (pintype "passive"))
      (node (ref "Q2") (pin "2") (pinfunction "E_2") (pintype "passive"))
      (node (ref "Q3") (pin "2") (pinfunction "E_2") (pintype "passive"))
      (node (ref "Q4") (pin "2") (pinfunction "E_2") (pintype "passive"))
      (node (ref "Q5") (pin "2") (pinfunction "E_2") (pintype "passive"))
      (node (ref "Q6") (pin "2") (pinfunction "E_2") (pintype "passive"))
      (node (ref "R17") (pin "1") (pinfunction "1_1") (pintype "passive"))
      (node (ref "R18") (pin "1") (pinfunction "1_1") (pintype "passive"))
      (node (ref "R19") (pin "1") (pinfunction "1_1") (pintype "passive"))
      (node (ref "R20") (pin "1") (pinfunction "1_1") (pintype "passive"))
      (node (ref "R22") (pin "1") (pinfunction "1_1") (pintype "passive"))
      (node (ref "R24") (pin "1") (pinfunction "1_1") (pintype "passive"))
      (node (ref "R26") (pin "1") (pinfunction "1_1") (pintype "passive"))
      (node (ref "R28") (pin "1") (pinfunction "1_1") (pintype "passive"))
      (node (ref "R29") (pin "1") (pinfunction "A_1") (pintype "passive"))
      (node (ref "R35") (pin "1") (pinfunction "1_1") (pintype "passive"))
      (node (ref "R38") (pin "1") (pinfunction "1_1") (pintype "passive"))
      (node (ref "R4") (pin "1") (pinfunction "1_1") (pintype "passive"))
      (node (ref "R5") (pin "1") (pinfunction "1_1") (pintype "passive"))
      (node (ref "R6") (pin "1") (pinfunction "1_1") (pintype "passive"))
      (node (ref "R7") (pin "1") (pinfunction "1_1") (pintype "passive"))
      (node (ref "R8") (pin "1") (pinfunction "1_1") (pintype "passive"))
      (node (ref "U1") (pin "1") (pinfunction "GND_1") (pintype "bidirectional"))
      (node (ref "U2") (pin "COM") (pinfunction "GND_COM") (pintype "bidirectional"))
      (node (ref "U3") (pin "2") (pinfunction "GND_2") (pintype "bidirectional"))
      (node (ref "U4") (pin "2") (pinfunction "GND_2") (pintype "bidirectional"))
      (node (ref "U5") (pin "2") (pinfunction "GND_2") (pintype "bidirectional"))
      (node (ref "U6") (pin "2") (pinfunction "GND_2") (pintype "bidirectional"))
      (node (ref "U7") (pin "25") (pinfunction "GND_25") (pintype "bidirectional"))
    )
    (net (code "22") (name "GPS_SCL") (class "Default")
      (node (ref "J6") (pin "1") (pinfunction "1_1") (pintype "bidirectional"))
      (node (ref "U7") (pin "21") (pinfunction "12/SCL_21") (pintype "bidirectional"))
    )
    (net (code "23") (name "GPS_SDA") (class "Default")
      (node (ref "J6") (pin "2") (pinfunction "2_2") (pintype "bidirectional"))
      (node (ref "U7") (pin "20") (pinfunction "11/SDA_20") (pintype "bidirectional"))
    )
    (net (code "24") (name "IN_LED2_ON") (class "Default")
      (node (ref "R37") (pin "1") (pinfunction "1_1") (pintype "passive"))
      (node (ref "U7") (pin "15") (pinfunction "6_15") (pintype "bidirectional"))
    )
    (net (code "25") (name "IN_LED3_ON") (class "Default")
      (node (ref "R40") (pin "1") (pinfunction "1_1") (pintype "passive"))
      (node (ref "U7") (pin "16") (pinfunction "7_16") (pintype "bidirectional"))
    )
    (net (code "26") (name "LED1") (class "Default")
      (node (ref "D1") (pin "A") (pinfunction "A_A") (pintype "passive"))
      (node (ref "IC2") (pin "16") (pinfunction "COL_16") (pintype "passive"))
      (node (ref "J1") (pin "12") (pinfunction "5_12") (pintype "bidirectional"))
      (node (ref "K1") (pin "9") (pinfunction "2_9") (pintype "passive"))
      (node (ref "Q1") (pin "3") (pinfunction "C_3") (pintype "passive"))
    )
    (net (code "27") (name "LED1_ON") (class "Default")
      (node (ref "Q1") (pin "1") (pinfunction "B_1") (pintype "passive"))
      (node (ref "Q5") (pin "1") (pinfunction "B_1") (pintype "passive"))
      (node (ref "R13") (pin "1") (pinfunction "1_1") (pintype "passive"))
      (node (ref "R17") (pin "2") (pinfunction "2_2") (pintype "passive"))
      (node (ref "R35") (pin "2") (pinfunction "2_2") (pintype "passive"))
      (node (ref "R37") (pin "2") (pinfunction "2_2") (pintype "passive"))
    )
    (net (code "28") (name "LED2") (class "Default")
      (node (ref "J1") (pin "11") (pinfunction "6_11") (pintype "bidirectional"))
      (node (ref "Q2") (pin "3") (pinfunction "C_3") (pintype "passive"))
    )
    (net (code "29") (name "LED2_ON") (class "Default")
      (node (ref "Q2") (pin "1") (pinfunction "B_1") (pintype "passive"))
      (node (ref "R14") (pin "1") (pinfunction "1_1") (pintype "passive"))
      (node (ref "R18") (pin "2") (pinfunction "2_2") (pintype "passive"))
    )
    (net (code "30") (name "LED3") (class "Default")
      (node (ref "J1") (pin "10") (pinfunction "7_10") (pintype "bidirectional"))
      (node (ref "Q3") (pin "3") (pinfunction "C_3") (pintype "passive"))
    )
    (net (code "31") (name "LED3_ON") (class "Default")
      (node (ref "Q3") (pin "1") (pinfunction "B_1") (pintype "passive"))
      (node (ref "R15") (pin "1") (pinfunction "1_1") (pintype "passive"))
      (node (ref "R19") (pin "2") (pinfunction "2_2") (pintype "passive"))
    )
    (net (code "32") (name "LED4") (class "Default")
      (node (ref "J1") (pin "9") (pinfunction "8_9") (pintype "bidirectional"))
      (node (ref "Q4") (pin "3") (pinfunction "C_3") (pintype "passive"))
    )
    (net (code "33") (name "LED4_ON") (class "Default")
      (node (ref "Q4") (pin "1") (pinfunction "B_1") (pintype "passive"))
      (node (ref "R16") (pin "1") (pinfunction "1_1") (pintype "passive"))
      (node (ref "R20") (pin "2") (pinfunction "2_2") (pintype "passive"))
    )
    (net (code "34") (name "Net-(B1-AC2)") (class "Default")
      (node (ref "B1") (pin "AC1") (pinfunction "AC2_AC1") (pintype "passive"))
      (node (ref "T1") (pin "6") (pinfunction "6_6") (pintype "passive"))
      (node (ref "T1") (pin "8") (pinfunction "8_8") (pintype "passive"))
    )
    (net (code "35") (name "Net-(C7-Pad1)") (class "Default")
      (node (ref "C7") (pin "1") (pinfunction "1_1") (pintype "passive"))
      (node (ref "R2") (pin "1") (pinfunction "1_1") (pintype "passive"))
      (node (ref "R3") (pin "2") (pinfunction "2_2") (pintype "passive"))
    )
    (net (code "36") (name "Net-(CONN_1-Pad1)") (class "Default")
      (node (ref "CONN_1") (pin "1") (pinfunction "1_1") (pintype "bidirectional"))
      (node (ref "T1") (pin "1") (pinfunction "1_1") (pintype "passive"))
      (node (ref "T1") (pin "4") (pinfunction "4_4") (pintype "passive"))
    )
    (net (code "37") (name "Net-(CONN_1-Pad2)") (class "Default")
      (node (ref "CONN_1") (pin "2") (pinfunction "2_2") (pintype "bidirectional"))
      (node (ref "T1") (pin "2") (pinfunction "2_2") (pintype "passive"))
      (node (ref "T1") (pin "3") (pinfunction "3_3") (pintype "passive"))
    )
    (net (code "38") (name "Net-(IC1A-I1)") (class "Default")
      (node (ref "IC1") (pin "2") (pinfunction "I1_2") (pintype "input"))
      (node (ref "U3") (pin "5") (pinfunction "OUT_5") (pintype "bidirectional"))
    )
    (net (code "39") (name "Net-(IC1A-O)") (class "Default")
      (node (ref "IC1") (pin "3") (pinfunction "O_3") (pintype "output"))
      (node (ref "R9") (pin "1") (pinfunction "1_1") (pintype "passive"))
    )
    (net (code "40") (name "Net-(IC1B-I1)") (class "Default")
      (node (ref "IC1") (pin "5") (pinfunction "I1_5") (pintype "input"))
      (node (ref "U4") (pin "5") (pinfunction "OUT_5") (pintype "bidirectional"))
    )
    (net (code "41") (name "Net-(IC1B-O)") (class "Default")
      (node (ref "IC1") (pin "6") (pinfunction "O_6") (pintype "output"))
      (node (ref "R10") (pin "1") (pinfunction "1_1") (pintype "passive"))
    )
    (net (code "42") (name "Net-(IC1C-I1)") (class "Default")
      (node (ref "IC1") (pin "10") (pinfunction "I1_10") (pintype "input"))
      (node (ref "U5") (pin "5") (pinfunction "OUT_5") (pintype "bidirectional"))
    )
    (net (code "43") (name "Net-(IC1C-O)") (class "Default")
      (node (ref "IC1") (pin "8") (pinfunction "O_8") (pintype "output"))
      (node (ref "R11") (pin "1") (pinfunction "1_1") (pintype "passive"))
    )
    (net (code "44") (name "Net-(IC1D-I1)") (class "Default")
      (node (ref "IC1") (pin "13") (pinfunction "I1_13") (pintype "input"))
      (node (ref "U6") (pin "5") (pinfunction "OUT_5") (pintype "bidirectional"))
    )
    (net (code "45") (name "Net-(IC1D-O)") (class "Default")
      (node (ref "IC1") (pin "11") (pinfunction "O_11") (pintype "output"))
      (node (ref "R12") (pin "1") (pinfunction "1_1") (pintype "passive"))
    )
    (net (code "46") (name "Net-(IC2A-A)") (class "Default")
      (node (ref "IC2") (pin "1") (pinfunction "A_1") (pintype "passive"))
      (node (ref "R9") (pin "2") (pinfunction "2_2") (pintype "passive"))
    )
    (net (code "47") (name "Net-(IC2B-A)") (class "Default")
      (node (ref "IC2") (pin "3") (pinfunction "A_3") (pintype "passive"))
      (node (ref "R10") (pin "2") (pinfunction "2_2") (pintype "passive"))
    )
    (net (code "48") (name "Net-(IC2B-COL)") (class "Default")
      (node (ref "D2") (pin "A") (pinfunction "A_A") (pintype "passive"))
      (node (ref "IC2") (pin "14") (pinfunction "COL_14") (pintype "passive"))
      (node (ref "K2") (pin "9") (pinfunction "2_9") (pintype "passive"))
    )
    (net (code "49") (name "Net-(IC2C-A)") (class "Default")
      (node (ref "IC2") (pin "5") (pinfunction "A_5") (pintype "passive"))
      (node (ref "R11") (pin "2") (pinfunction "2_2") (pintype "passive"))
    )
    (net (code "50") (name "Net-(IC2C-COL)") (class "Default")
      (node (ref "D3") (pin "A") (pinfunction "A_A") (pintype "passive"))
      (node (ref "IC2") (pin "12") (pinfunction "COL_12") (pintype "passive"))
      (node (ref "K3") (pin "9") (pinfunction "2_9") (pintype "passive"))
    )
    (net (code "51") (name "Net-(IC2D-A)") (class "Default")
      (node (ref "IC2") (pin "7") (pinfunction "A_7") (pintype "passive"))
      (node (ref "R12") (pin "2") (pinfunction "2_2") (pintype "passive"))
    )
    (net (code "52") (name "Net-(IC2D-COL)") (class "Default")
      (node (ref "D4") (pin "A") (pinfunction "A_A") (pintype "passive"))
      (node (ref "IC2") (pin "10") (pinfunction "COL_10") (pintype "passive"))
      (node (ref "K4") (pin "9") (pinfunction "2_9") (pintype "passive"))
    )
    (net (code "53") (name "Net-(IC3A-+IN)") (class "Default")
      (node (ref "IC3") (pin "3") (pinfunction "+IN_3") (pintype "input"))
      (node (ref "J7") (pin "2") (pinfunction "2_2") (pintype "bidirectional"))
      (node (ref "R30") (pin "1") (pinfunction "1_1") (pintype "passive"))
    )
    (net (code "54") (name "Net-(IC3A--IN)") (class "Default")
      (node (ref "IC3") (pin "2") (pinfunction "-IN_2") (pintype "input"))
      (node (ref "IC3") (pin "6") (pinfunction "-IN_6") (pintype "input"))
      (node (ref "IC4") (pin "2") (pinfunction "-IN_2") (pintype "input"))
      (node (ref "IC4") (pin "6") (pinfunction "-IN_6") (pintype "input"))
      (node (ref "IC5") (pin "2") (pinfunction "-IN_2") (pintype "input"))
      (node (ref "R29") (pin "2") (pinfunction "S_2") (pintype "passive"))
    )
    (net (code "55") (name "Net-(IC3A-OUT)") (class "Default")
      (node (ref "IC3") (pin "1") (pinfunction "OUT_1") (pintype "output"))
      (node (ref "IC6") (pin "3") (pinfunction "I_3") (pintype "input"))
    )
    (net (code "56") (name "Net-(IC3B-+IN)") (class "Default")
      (node (ref "IC3") (pin "5") (pinfunction "+IN_5") (pintype "input"))
      (node (ref "J8") (pin "2") (pinfunction "2_2") (pintype "bidirectional"))
      (node (ref "R31") (pin "1") (pinfunction "1_1") (pintype "passive"))
    )
    (net (code "57") (name "Net-(IC3B-OUT)") (class "Default")
      (node (ref "IC3") (pin "7") (pinfunction "OUT_7") (pintype "output"))
      (node (ref "IC6") (pin "5") (pinfunction "I_5") (pintype "input"))
    )
    (net (code "58") (name "Net-(IC4A-+IN)") (class "Default")
      (node (ref "IC4") (pin "3") (pinfunction "+IN_3") (pintype "input"))
      (node (ref "J9") (pin "2") (pinfunction "2_2") (pintype "bidirectional"))
      (node (ref "R32") (pin "1") (pinfunction "1_1") (pintype "passive"))
    )
    (net (code "59") (name "Net-(IC4A-OUT)") (class "Default")
      (node (ref "IC4") (pin "1") (pinfunction "OUT_1") (pintype "output"))
      (node (ref "IC6") (pin "7") (pinfunction "I_7") (pintype "input"))
    )
    (net (code "60") (name "Net-(IC4B-+IN)") (class "Default")
      (node (ref "IC4") (pin "5") (pinfunction "+IN_5") (pintype "input"))
      (node (ref "J10") (pin "2") (pinfunction "2_2") (pintype "bidirectional"))
      (node (ref "R33") (pin "1") (pinfunction "1_1") (pintype "passive"))
    )
    (net (code "61") (name "Net-(IC4B-OUT)") (class "Default")
      (node (ref "IC4") (pin "7") (pinfunction "OUT_7") (pintype "output"))
      (node (ref "IC6") (pin "9") (pinfunction "I_9") (pintype "input"))
    )
    (net (code "62") (name "Net-(IC5A-+IN)") (class "Default")
      (node (ref "IC5") (pin "3") (pinfunction "+IN_3") (pintype "input"))
      (node (ref "J11") (pin "2") (pinfunction "2_2") (pintype "bidirectional"))
      (node (ref "R34") (pin "1") (pinfunction "1_1") (pintype "passive"))
    )
    (net (code "63") (name "Net-(IC5A-OUT)") (class "Default")
      (node (ref "IC5") (pin "1") (pinfunction "OUT_1") (pintype "output"))
      (node (ref "IC6") (pin "11") (pinfunction "I_11") (pintype "input"))
    )
    (net (code "64") (name "Net-(K1B-S)") (class "Default")
      (node (ref "J2") (pin "2") (pinfunction "2_2") (pintype "bidirectional"))
      (node (ref "K1") (pin "10") (pinfunction "S_10") (pintype "passive"))
    )
    (net (code "65") (name "Net-(K2B-S)") (class "Default")
      (node (ref "J3") (pin "2") (pinfunction "2_2") (pintype "bidirectional"))
      (node (ref "K2") (pin "10") (pinfunction "S_10") (pintype "passive"))
    )
    (net (code "66") (name "Net-(K3B-S)") (class "Default")
      (node (ref "J4") (pin "2") (pinfunction "2_2") (pintype "bidirectional"))
      (node (ref "K3") (pin "10") (pinfunction "S_10") (pintype "passive"))
    )
    (net (code "67") (name "Net-(K4B-S)") (class "Default")
      (node (ref "J5") (pin "2") (pinfunction "2_2") (pintype "bidirectional"))
      (node (ref "K4") (pin "10") (pinfunction "S_10") (pintype "passive"))
    )
    (net (code "68") (name "Net-(LED1-PadA)") (class "Default")
      (node (ref "LED1") (pin "A") (pinfunction "A_A") (pintype "passive"))
      (node (ref "R41") (pin "1") (pinfunction "1_1") (pintype "passive"))
    )
    (net (code "69") (name "Net-(LED2-PadA)") (class "Default")
      (node (ref "LED2") (pin "A") (pinfunction "A_A") (pintype "passive"))
      (node (ref "R36") (pin "1") (pinfunction "1_1") (pintype "passive"))
    )
    (net (code "70") (name "Net-(LED3-PadA)") (class "Default")
      (node (ref "LED3") (pin "A") (pinfunction "A_A") (pintype "passive"))
      (node (ref "R39") (pin "1") (pinfunction "1_1") (pintype "passive"))
    )
    (net (code "71") (name "Net-(Q5-C)") (class "Default")
      (node (ref "LED2") (pin "C") (pinfunction "C_C") (pintype "passive"))
      (node (ref "Q5") (pin "3") (pinfunction "C_3") (pintype "passive"))
    )
    (net (code "72") (name "Net-(Q6-B)") (class "Default")
      (node (ref "Q6") (pin "1") (pinfunction "B_1") (pintype "passive"))
      (node (ref "R38") (pin "2") (pinfunction "2_2") (pintype "passive"))
      (node (ref "R40") (pin "2") (pinfunction "2_2") (pintype "passive"))
    )
    (net (code "73") (name "Net-(Q6-C)") (class "Default")
      (node (ref "LED3") (pin "C") (pinfunction "C_C") (pintype "passive"))
      (node (ref "Q6") (pin "3") (pinfunction "C_3") (pintype "passive"))
    )
    (net (code "74") (name "Net-(U1-BOOT)") (class "Default")
      (node (ref "C4") (pin "1") (pinfunction "1_1") (pintype "passive"))
      (node (ref "U1") (pin "6") (pinfunction "BOOT_6") (pintype "bidirectional"))
    )
    (net (code "75") (name "Net-(U1-EN)") (class "Default")
      (node (ref "R1") (pin "2") (pinfunction "2_2") (pintype "passive"))
      (node (ref "U1") (pin "5") (pinfunction "EN_5") (pintype "bidirectional"))
    )
    (net (code "76") (name "Net-(U1-FB)") (class "Default")
      (node (ref "C7") (pin "2") (pinfunction "2_2") (pintype "passive"))
      (node (ref "R3") (pin "1") (pinfunction "1_1") (pintype "passive"))
      (node (ref "R4") (pin "2") (pinfunction "2_2") (pintype "passive"))
      (node (ref "U1") (pin "4") (pinfunction "FB_4") (pintype "bidirectional"))
    )
    (net (code "77") (name "Net-(U1-SW)") (class "Default")
      (node (ref "C4") (pin "2") (pinfunction "2_2") (pintype "passive"))
      (node (ref "L1") (pin "1") (pinfunction "1_1") (pintype "passive"))
      (node (ref "U1") (pin "2") (pinfunction "SW_2") (pintype "bidirectional"))
    )
    (net (code "78") (name "V1_FB") (class "Default")
      (node (ref "R21") (pin "1") (pinfunction "1_1") (pintype "passive"))
      (node (ref "R22") (pin "2") (pinfunction "2_2") (pintype "passive"))
      (node (ref "U7") (pin "2") (pinfunction "DAC0/A0_2") (pintype "bidirectional"))
    )
    (net (code "79") (name "V2_FB") (class "Default")
      (node (ref "R23") (pin "1") (pinfunction "1_1") (pintype "passive"))
      (node (ref "R24") (pin "2") (pinfunction "2_2") (pintype "passive"))
      (node (ref "U7") (pin "11") (pinfunction "~{2}_11") (pintype "bidirectional"))
    )
    (net (code "80") (name "V3_FB") (class "Default")
      (node (ref "R25") (pin "1") (pinfunction "1_1") (pintype "passive"))
      (node (ref "R26") (pin "2") (pinfunction "2_2") (pintype "passive"))
      (node (ref "U7") (pin "12") (pinfunction "~{3}_12") (pintype "bidirectional"))
    )
    (net (code "81") (name "V4_FB") (class "Default")
      (node (ref "R27") (pin "1") (pinfunction "1_1") (pintype "passive"))
      (node (ref "R28") (pin "2") (pinfunction "2_2") (pintype "passive"))
      (node (ref "U7") (pin "14") (pinfunction "~{5}_14") (pintype "bidirectional"))
    )
    (net (code "82") (name "VDIG1") (class "Default")
      (node (ref "IC1") (pin "1") (pinfunction "I0_1") (pintype "input"))
      (node (ref "U7") (pin "5") (pinfunction "A3_5") (pintype "bidirectional"))
    )
    (net (code "83") (name "VDIG2") (class "Default")
      (node (ref "IC1") (pin "4") (pinfunction "I0_4") (pintype "input"))
      (node (ref "U7") (pin "6") (pinfunction "A4_6") (pintype "bidirectional"))
    )
    (net (code "84") (name "VDIG3") (class "Default")
      (node (ref "IC1") (pin "9") (pinfunction "I0_9") (pintype "input"))
      (node (ref "U7") (pin "7") (pinfunction "A5_7") (pintype "bidirectional"))
    )
    (net (code "85") (name "VDIG4") (class "Default")
      (node (ref "IC1") (pin "12") (pinfunction "I0_12") (pintype "input"))
      (node (ref "U7") (pin "8") (pinfunction "A6_8") (pintype "bidirectional"))
    )
    (net (code "86") (name "XB_RX") (class "Default")
      (node (ref "JP1") (pin "3") (pinfunction "DIN_3") (pintype "input"))
      (node (ref "U7") (pin "17") (pinfunction "8/MOSI_17") (pintype "bidirectional"))
    )
    (net (code "87") (name "XB_TX") (class "Default")
      (node (ref "JP1") (pin "2") (pinfunction "DOUT_2") (pintype "output"))
      (node (ref "U7") (pin "18") (pinfunction "9/SCK_18") (pintype "bidirectional"))
    )
    (net (code "88") (name "unconnected-(IC2D-EMIT-Pad9)") (class "Default")
      (node (ref "IC2") (pin "9") (pinfunction "EMIT_9") (pintype "passive"))
    )
    (net (code "89") (name "unconnected-(JP1-CTS-Pad12)") (class "Default")
      (node (ref "JP1") (pin "12") (pinfunction "CTS_12") (pintype "output"))
    )
    (net (code "90") (name "unconnected-(JP1-DIO0-Pad20)") (class "Default")
      (node (ref "JP1") (pin "20") (pinfunction "DIO0_20") (pintype "bidirectional"))
    )
    (net (code "91") (name "unconnected-(JP1-DIO1-Pad19)") (class "Default")
      (node (ref "JP1") (pin "19") (pinfunction "DIO1_19") (pintype "bidirectional"))
    )
    (net (code "92") (name "unconnected-(JP1-DIO2-Pad18)") (class "Default")
      (node (ref "JP1") (pin "18") (pinfunction "DIO2_18") (pintype "bidirectional"))
    )
    (net (code "93") (name "unconnected-(JP1-DIO3-Pad17)") (class "Default")
      (node (ref "JP1") (pin "17") (pinfunction "DIO3_17") (pintype "bidirectional"))
    )
    (net (code "94") (name "unconnected-(JP1-DIO4-Pad11)") (class "Default")
      (node (ref "JP1") (pin "11") (pinfunction "DIO4_11") (pintype "bidirectional"))
    )
    (net (code "95") (name "unconnected-(JP1-DIO5-Pad15)") (class "Default")
      (node (ref "JP1") (pin "15") (pinfunction "DIO5_15") (pintype "bidirectional"))
    )
    (net (code "96") (name "unconnected-(JP1-DIO9-Pad13)") (class "Default")
      (node (ref "JP1") (pin "13") (pinfunction "DIO9_13") (pintype "bidirectional"))
    )
    (net (code "97") (name "unconnected-(JP1-DIO11-Pad7)") (class "Default")
      (node (ref "JP1") (pin "7") (pinfunction "DIO11_7") (pintype "bidirectional"))
    )
    (net (code "98") (name "unconnected-(JP1-DIO12-Pad4)") (class "Default")
      (node (ref "JP1") (pin "4") (pinfunction "DIO12_4") (pintype "bidirectional"))
    )
    (net (code "99") (name "unconnected-(JP1-DTR-Pad9)") (class "Default")
      (node (ref "JP1") (pin "9") (pinfunction "DTR_9") (pintype "bidirectional"))
    )
    (net (code "100") (name "unconnected-(JP1-RES-Pad8)") (class "Default")
      (node (ref "JP1") (pin "8") (pinfunction "RES_8") (pintype "bidirectional"))
    )
    (net (code "101") (name "unconnected-(JP1-RES-Pad14)") (class "Default")
      (node (ref "JP1") (pin "14") (pinfunction "RES_14") (pintype "bidirectional"))
    )
    (net (code "102") (name "unconnected-(JP1-RESET-Pad5)") (class "Default")
      (node (ref "JP1") (pin "5") (pinfunction "RESET_5") (pintype "input"))
    )
    (net (code "103") (name "unconnected-(JP1-RSSI-Pad6)") (class "Default")
      (node (ref "JP1") (pin "6") (pinfunction "RSSI_6") (pintype "bidirectional"))
    )
    (net (code "104") (name "unconnected-(JP1-RTS-Pad16)") (class "Default")
      (node (ref "JP1") (pin "16") (pinfunction "RTS_16") (pintype "input"))
    )
    (net (code "105") (name "unconnected-(K1B-O-Pad1)") (class "Default")
      (node (ref "K1") (pin "1") (pinfunction "O_1") (pintype "passive"))
    )
    (net (code "106") (name "unconnected-(K2B-O-Pad1)") (class "Default")
      (node (ref "K2") (pin "1") (pinfunction "O_1") (pintype "passive"))
    )
    (net (code "107") (name "unconnected-(K3B-O-Pad1)") (class "Default")
      (node (ref "K3") (pin "1") (pinfunction "O_1") (pintype "passive"))
    )
    (net (code "108") (name "unconnected-(K4B-O-Pad1)") (class "Default")
      (node (ref "K4") (pin "1") (pinfunction "O_1") (pintype "passive"))
    )
    (net (code "109") (name "unconnected-(U3-~{OUT}-Pad4)") (class "Default")
      (node (ref "U3") (pin "4") (pinfunction "~{OUT}_4") (pintype "bidirectional"))
    )
    (net (code "110") (name "unconnected-(U4-~{OUT}-Pad4)") (class "Default")
      (node (ref "U4") (pin "4") (pinfunction "~{OUT}_4") (pintype "bidirectional"))
    )
    (net (code "111") (name "unconnected-(U5-~{OUT}-Pad4)") (class "Default")
      (node (ref "U5") (pin "4") (pinfunction "~{OUT}_4") (pintype "bidirectional"))
    )
    (net (code "112") (name "unconnected-(U6-~{OUT}-Pad4)") (class "Default")
      (node (ref "U6") (pin "4") (pinfunction "~{OUT}_4") (pintype "bidirectional"))
    )
    (net (code "113") (name "unconnected-(U7-5V-Pad28)") (class "Default")
      (node (ref "U7") (pin "28") (pinfunction "5V_28") (pintype "bidirectional"))
    )
    (net (code "114") (name "unconnected-(U7-10{slash}MISO-Pad19)") (class "Default")
      (node (ref "U7") (pin "19") (pinfunction "10/MISO_19") (pintype "bidirectional"))
    )
    (net (code "115") (name "unconnected-(U7-AREF-Pad1)") (class "Default")
      (node (ref "U7") (pin "1") (pinfunction "AREF_1") (pintype "bidirectional"))
    )
    (net (code "116") (name "unconnected-(U7-RESET-Pad24)") (class "Default")
      (node (ref "U7") (pin "24") (pinfunction "RESET_24") (pintype "bidirectional"))
    )
    (net (code "117") (name "unconnected-(U7-VCC-Pad26)") (class "Default")
      (node (ref "U7") (pin "26") (pinfunction "VCC_26") (pintype "bidirectional"))
    )
  )
)
